# Arduino_PRO_Portenta_H7_Carrier_Shield.net
KiCad netlist of a schematic drawn in EasyEDA
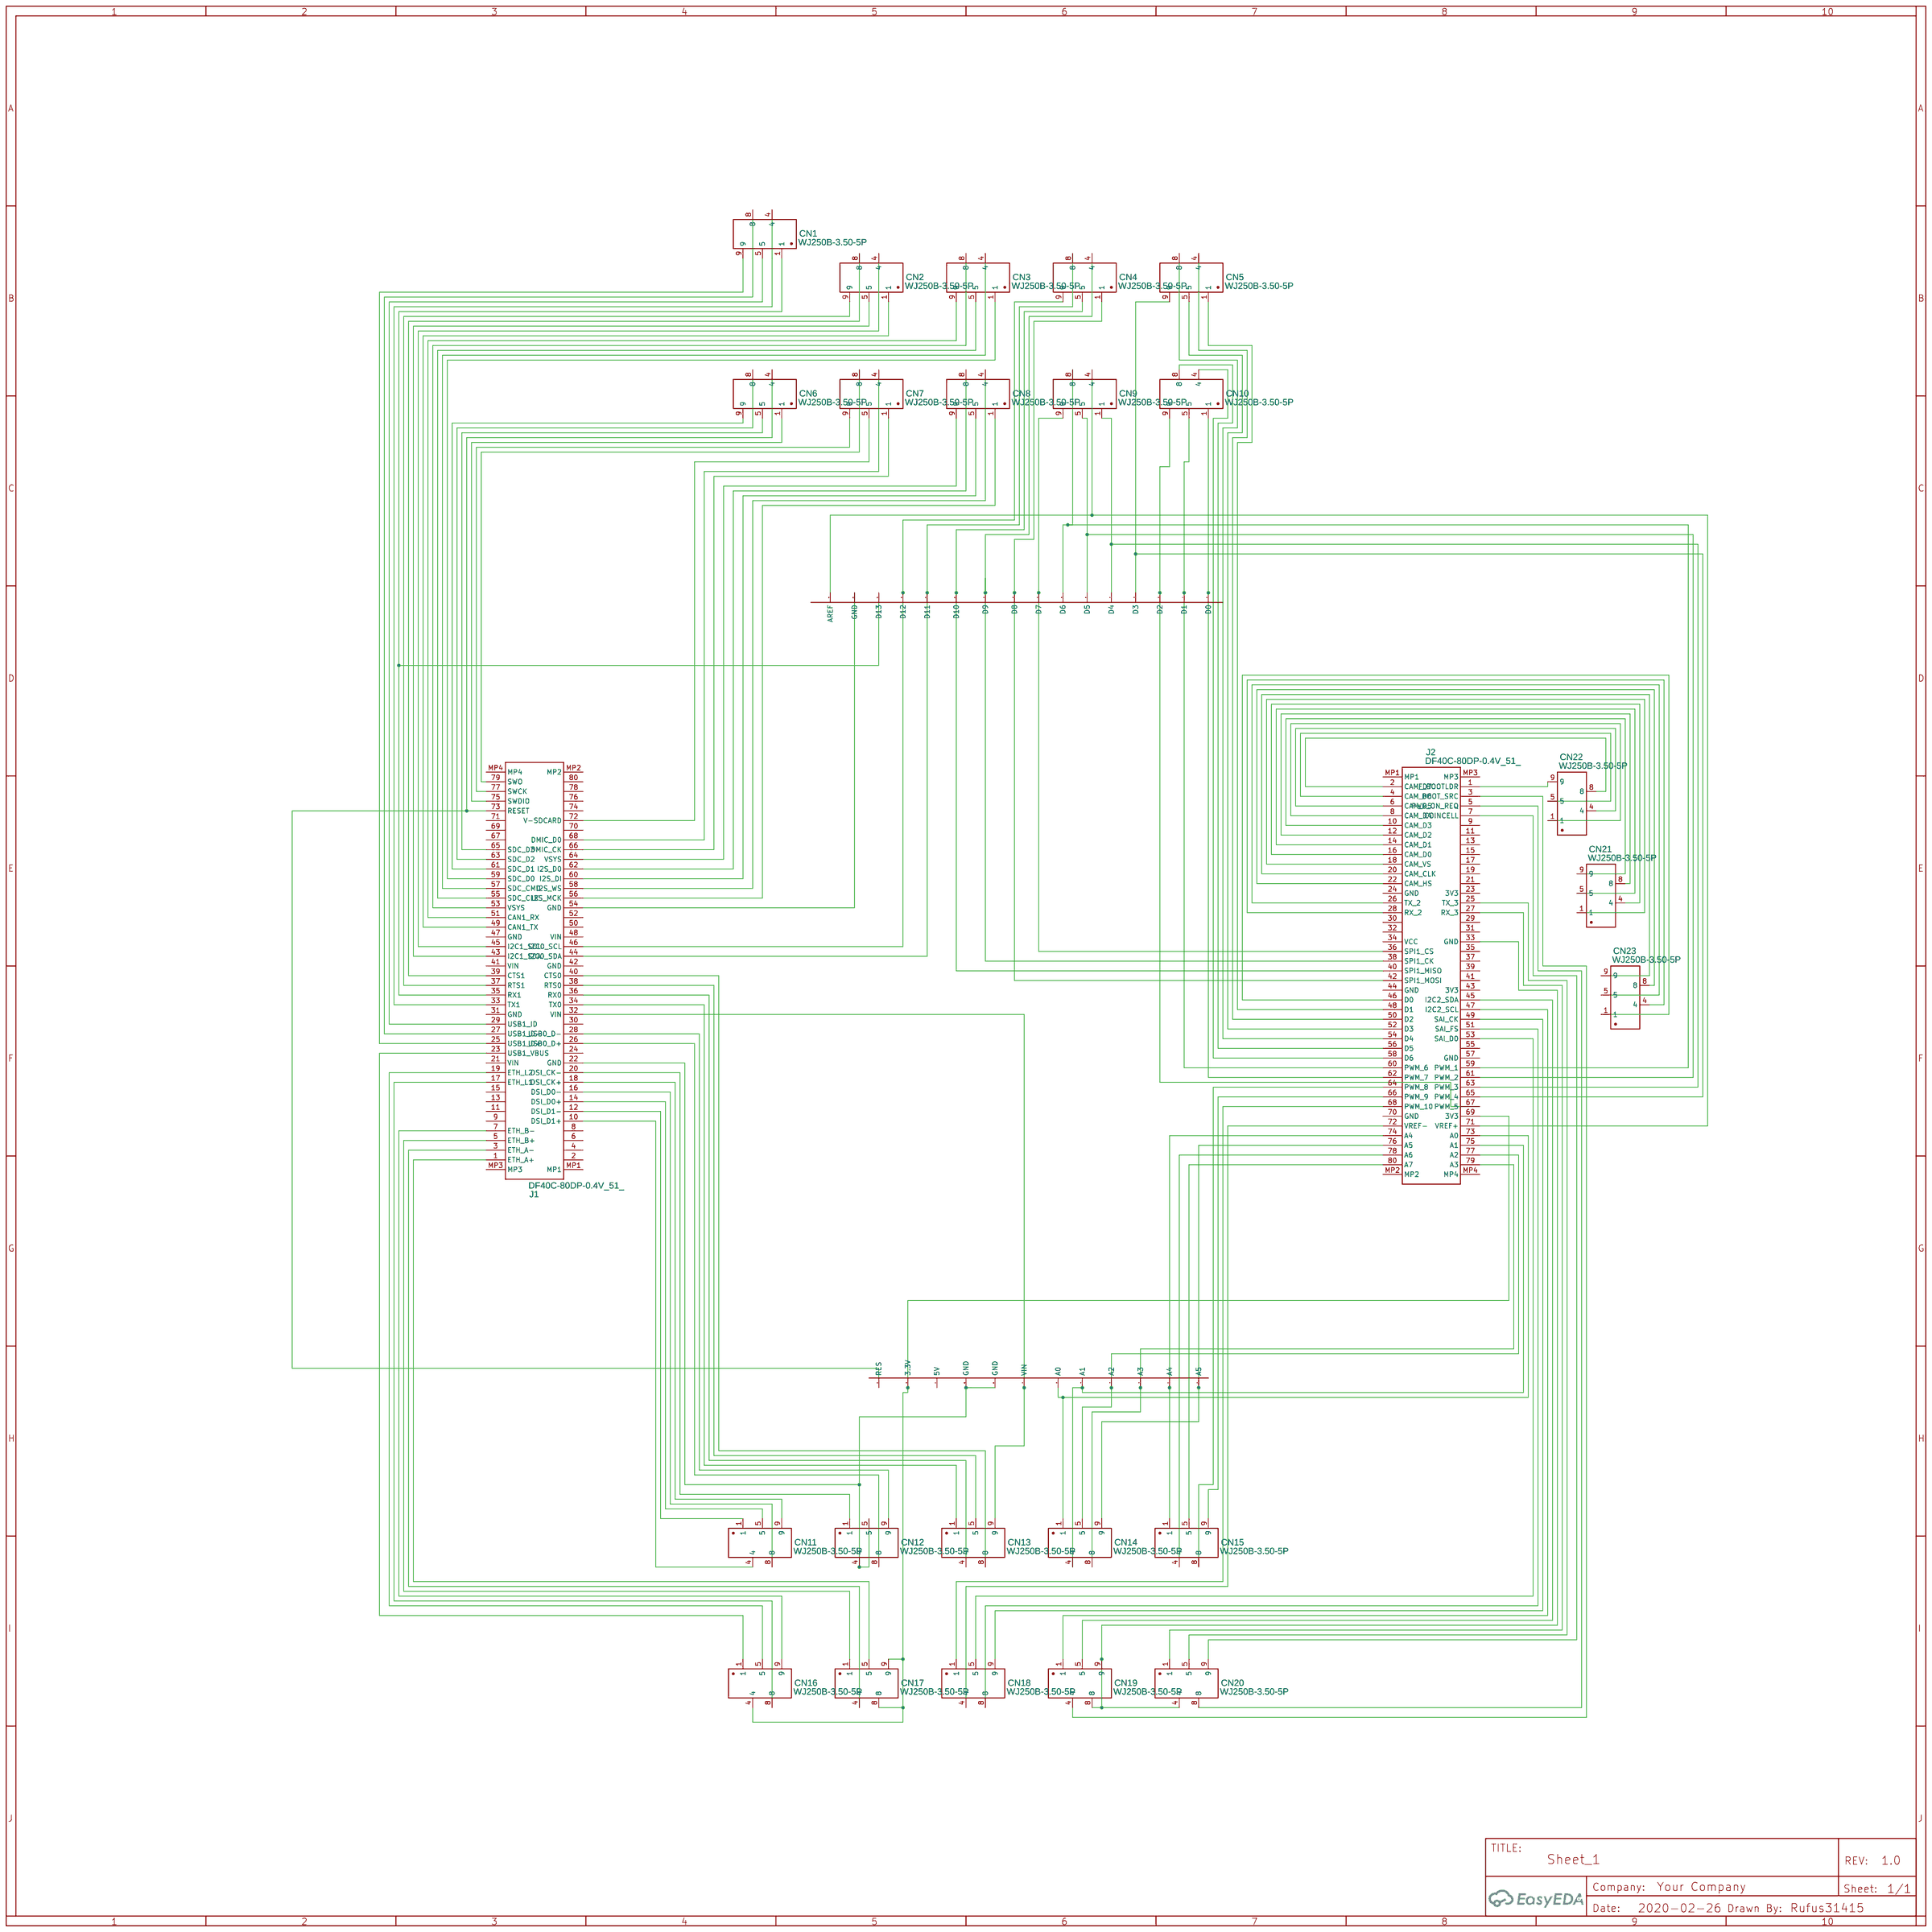
[diagram p0: schematic sheet]

(export (version "E")
  (design (tool "Eeschema 10.0.6"))
  (components
    (comp (ref "CN1")
      (value "WJ250B-3.50-5P")
      (fields (field (name "Manufacturer") "ReliaPro"))
      (libsource (lib "") (part "WJ250B-3.50-5P"))
    )
    (comp (ref "CN2")
      (value "WJ250B-3.50-5P")
      (fields (field (name "Manufacturer") "ReliaPro"))
      (libsource (lib "") (part "WJ250B-3.50-5P"))
    )
    (comp (ref "CN3")
      (value "WJ250B-3.50-5P")
      (fields (field (name "Manufacturer") "ReliaPro"))
      (libsource (lib "") (part "WJ250B-3.50-5P"))
    )
    (comp (ref "CN4")
      (value "WJ250B-3.50-5P")
      (fields (field (name "Manufacturer") "ReliaPro"))
      (libsource (lib "") (part "WJ250B-3.50-5P"))
    )
    (comp (ref "CN5")
      (value "WJ250B-3.50-5P")
      (fields (field (name "Manufacturer") "ReliaPro"))
      (libsource (lib "") (part "WJ250B-3.50-5P"))
    )
    (comp (ref "CN6")
      (value "WJ250B-3.50-5P")
      (fields (field (name "Manufacturer") "ReliaPro"))
      (libsource (lib "") (part "WJ250B-3.50-5P"))
    )
    (comp (ref "CN7")
      (value "WJ250B-3.50-5P")
      (fields (field (name "Manufacturer") "ReliaPro"))
      (libsource (lib "") (part "WJ250B-3.50-5P"))
    )
    (comp (ref "CN8")
      (value "WJ250B-3.50-5P")
      (fields (field (name "Manufacturer") "ReliaPro"))
      (libsource (lib "") (part "WJ250B-3.50-5P"))
    )
    (comp (ref "CN9")
      (value "WJ250B-3.50-5P")
      (fields (field (name "Manufacturer") "ReliaPro"))
      (libsource (lib "") (part "WJ250B-3.50-5P"))
    )
    (comp (ref "CN10")
      (value "WJ250B-3.50-5P")
      (fields (field (name "Manufacturer") "ReliaPro"))
      (libsource (lib "") (part "WJ250B-3.50-5P"))
    )
    (comp (ref "CN11")
      (value "WJ250B-3.50-5P")
      (fields (field (name "Manufacturer") "ReliaPro"))
      (libsource (lib "") (part "WJ250B-3.50-5P_1"))
    )
    (comp (ref "CN12")
      (value "WJ250B-3.50-5P")
      (fields (field (name "Manufacturer") "ReliaPro"))
      (libsource (lib "") (part "WJ250B-3.50-5P_1"))
    )
    (comp (ref "CN13")
      (value "WJ250B-3.50-5P")
      (fields (field (name "Manufacturer") "ReliaPro"))
      (libsource (lib "") (part "WJ250B-3.50-5P_1"))
    )
    (comp (ref "CN14")
      (value "WJ250B-3.50-5P")
      (fields (field (name "Manufacturer") "ReliaPro"))
      (libsource (lib "") (part "WJ250B-3.50-5P_1"))
    )
    (comp (ref "CN15")
      (value "WJ250B-3.50-5P")
      (fields (field (name "Manufacturer") "ReliaPro"))
      (libsource (lib "") (part "WJ250B-3.50-5P_1"))
    )
    (comp (ref "CN16")
      (value "WJ250B-3.50-5P")
      (fields (field (name "Manufacturer") "ReliaPro"))
      (libsource (lib "") (part "WJ250B-3.50-5P_1"))
    )
    (comp (ref "CN17")
      (value "WJ250B-3.50-5P")
      (fields (field (name "Manufacturer") "ReliaPro"))
      (libsource (lib "") (part "WJ250B-3.50-5P_1"))
    )
    (comp (ref "CN18")
      (value "WJ250B-3.50-5P")
      (fields (field (name "Manufacturer") "ReliaPro"))
      (libsource (lib "") (part "WJ250B-3.50-5P_1"))
    )
    (comp (ref "CN19")
      (value "WJ250B-3.50-5P")
      (fields (field (name "Manufacturer") "ReliaPro"))
      (libsource (lib "") (part "WJ250B-3.50-5P_1"))
    )
    (comp (ref "CN20")
      (value "WJ250B-3.50-5P")
      (fields (field (name "Manufacturer") "ReliaPro"))
      (libsource (lib "") (part "WJ250B-3.50-5P_1"))
    )
    (comp (ref "CN21")
      (value "WJ250B-3.50-5P")
      (fields (field (name "Manufacturer") "ReliaPro"))
      (libsource (lib "") (part "WJ250B-3.50-5P_2"))
    )
    (comp (ref "CN22")
      (value "WJ250B-3.50-5P")
      (fields (field (name "Manufacturer") "ReliaPro"))
      (libsource (lib "") (part "WJ250B-3.50-5P_2"))
    )
    (comp (ref "CN23")
      (value "WJ250B-3.50-5P")
      (fields (field (name "Manufacturer") "ReliaPro"))
      (libsource (lib "") (part "WJ250B-3.50-5P_2"))
    )
    (comp (ref "J1") (value "DF40C-80DP-0.4V_51_") (libsource (lib "") (part "DF40C-80DP-0.4V_51__1")))
    (comp (ref "J2") (value "DF40C-80DP-0.4V_51_") (libsource (lib "") (part "DF40C-80DP-0.4V_51_")))
    (comp (ref "U1")
      (value "ARDUINO_SHIELDNO_SILK BIG")
      (libsource (lib "") (part "ARDUINO_SHIELDNO_SILK BIG"))
    )
  )
  (nets
    (net (code "1") (name "Net-(CN3-Pad8)") (class "Default")
      (node (ref "CN3") (pin "8") (pinfunction "8_8") (pintype "unspecified"))
      (node (ref "J1") (pin "53") (pinfunction "VSYS_53") (pintype "bidirectional"))
    )
    (net (code "2") (name "Net-(CN8-Pad9)") (class "Default")
      (node (ref "CN8") (pin "9") (pinfunction "9_9") (pintype "unspecified"))
      (node (ref "J1") (pin "64") (pinfunction "VSYS_64") (pintype "bidirectional"))
    )
    (net (code "3") (name "Net-(CN12-Pad4)") (class "Default")
      (node (ref "CN12") (pin "4") (pinfunction "4_4") (pintype "unspecified"))
      (node (ref "CN12") (pin "5") (pinfunction "5_5") (pintype "unspecified"))
      (node (ref "J1") (pin "22") (pinfunction "GND_22") (pintype "bidirectional"))
      (node (ref "U1") (pin "GND@0") (pinfunction "GND_GND@0") (pintype "unspecified"))
      (node (ref "U1") (pin "GND@1") (pinfunction "GND_GND@1") (pintype "unspecified"))
    )
    (net (code "4") (name "Net-(CN13-Pad9)") (class "Default")
      (node (ref "CN13") (pin "9") (pinfunction "9_9") (pintype "unspecified"))
      (node (ref "J1") (pin "32") (pinfunction "VIN_32") (pintype "bidirectional"))
      (node (ref "U1") (pin "VIN") (pinfunction "VIN_VIN") (pintype "unspecified"))
    )
    (net (code "5") (name "Net-(CN16-Pad4)") (class "Default")
      (node (ref "CN16") (pin "4") (pinfunction "4_4") (pintype "unspecified"))
      (node (ref "CN17") (pin "8") (pinfunction "8_8") (pintype "unspecified"))
      (node (ref "CN17") (pin "9") (pinfunction "9_9") (pintype "unspecified"))
      (node (ref "J2") (pin "69") (pinfunction "3V3_69") (pintype "bidirectional"))
      (node (ref "U1") (pin "3.3V") (pinfunction "3.3V_3.3V") (pintype "unspecified"))
    )
    (net (code "6") (name "Net-(CN19-Pad8)") (class "Default")
      (node (ref "CN19") (pin "8") (pinfunction "8_8") (pintype "unspecified"))
      (node (ref "CN19") (pin "9") (pinfunction "9_9") (pintype "unspecified"))
      (node (ref "CN20") (pin "4") (pinfunction "4_4") (pintype "unspecified"))
      (node (ref "J2") (pin "33") (pinfunction "GND_33") (pintype "bidirectional"))
    )
    (net (code "7") (name "Net-(J1-CAN1_RX)") (class "Default")
      (node (ref "CN3") (pin "9") (pinfunction "9_9") (pintype "unspecified"))
      (node (ref "J1") (pin "51") (pinfunction "CAN1_RX_51") (pintype "bidirectional"))
    )
    (net (code "8") (name "Net-(J1-CAN1_TX)") (class "Default")
      (node (ref "CN2") (pin "1") (pinfunction "1_1") (pintype "unspecified"))
      (node (ref "J1") (pin "49") (pinfunction "CAN1_TX_49") (pintype "bidirectional"))
    )
    (net (code "9") (name "Net-(J1-CTS0)") (class "Default")
      (node (ref "CN13") (pin "8") (pinfunction "8_8") (pintype "unspecified"))
      (node (ref "J1") (pin "40") (pinfunction "CTS0_40") (pintype "bidirectional"))
    )
    (net (code "10") (name "Net-(J1-CTS1)") (class "Default")
      (node (ref "CN2") (pin "8") (pinfunction "8_8") (pintype "unspecified"))
      (node (ref "J1") (pin "39") (pinfunction "CTS1_39") (pintype "bidirectional"))
    )
    (net (code "11") (name "Net-(J1-DMIC_CK)") (class "Default")
      (node (ref "CN7") (pin "1") (pinfunction "1_1") (pintype "unspecified"))
      (node (ref "J1") (pin "66") (pinfunction "DMIC_CK_66") (pintype "bidirectional"))
    )
    (net (code "12") (name "Net-(J1-DMIC_D0)") (class "Default")
      (node (ref "CN7") (pin "4") (pinfunction "4_4") (pintype "unspecified"))
      (node (ref "J1") (pin "68") (pinfunction "DMIC_D0_68") (pintype "bidirectional"))
    )
    (net (code "13") (name "Net-(J1-DSI_CK+)") (class "Default")
      (node (ref "CN11") (pin "9") (pinfunction "9_9") (pintype "unspecified"))
      (node (ref "J1") (pin "18") (pinfunction "DSI_CK+_18") (pintype "bidirectional"))
    )
    (net (code "14") (name "Net-(J1-DSI_CK-)") (class "Default")
      (node (ref "CN12") (pin "1") (pinfunction "1_1") (pintype "unspecified"))
      (node (ref "J1") (pin "20") (pinfunction "DSI_CK-_20") (pintype "bidirectional"))
    )
    (net (code "15") (name "Net-(J1-DSI_D0+)") (class "Default")
      (node (ref "CN11") (pin "5") (pinfunction "5_5") (pintype "unspecified"))
      (node (ref "J1") (pin "14") (pinfunction "DSI_D0+_14") (pintype "bidirectional"))
    )
    (net (code "16") (name "Net-(J1-DSI_D0-)") (class "Default")
      (node (ref "CN11") (pin "8") (pinfunction "8_8") (pintype "unspecified"))
      (node (ref "J1") (pin "16") (pinfunction "DSI_D0-_16") (pintype "bidirectional"))
    )
    (net (code "17") (name "Net-(J1-DSI_D1+)") (class "Default")
      (node (ref "CN11") (pin "4") (pinfunction "4_4") (pintype "unspecified"))
      (node (ref "J1") (pin "10") (pinfunction "DSI_D1+_10") (pintype "bidirectional"))
    )
    (net (code "18") (name "Net-(J1-DSI_D1-)") (class "Default")
      (node (ref "CN11") (pin "1") (pinfunction "1_1") (pintype "unspecified"))
      (node (ref "J1") (pin "12") (pinfunction "DSI_D1-_12") (pintype "bidirectional"))
    )
    (net (code "19") (name "Net-(J1-ETH_A+)") (class "Default")
      (node (ref "CN17") (pin "5") (pinfunction "5_5") (pintype "unspecified"))
      (node (ref "J1") (pin "1") (pinfunction "ETH_A+_1") (pintype "bidirectional"))
    )
    (net (code "20") (name "Net-(J1-ETH_A-)") (class "Default")
      (node (ref "CN17") (pin "4") (pinfunction "4_4") (pintype "unspecified"))
      (node (ref "J1") (pin "3") (pinfunction "ETH_A-_3") (pintype "bidirectional"))
    )
    (net (code "21") (name "Net-(J1-ETH_B+)") (class "Default")
      (node (ref "CN17") (pin "1") (pinfunction "1_1") (pintype "unspecified"))
      (node (ref "J1") (pin "5") (pinfunction "ETH_B+_5") (pintype "bidirectional"))
    )
    (net (code "22") (name "Net-(J1-ETH_B-)") (class "Default")
      (node (ref "CN16") (pin "9") (pinfunction "9_9") (pintype "unspecified"))
      (node (ref "J1") (pin "7") (pinfunction "ETH_B-_7") (pintype "bidirectional"))
    )
    (net (code "23") (name "Net-(J1-ETH_L1)") (class "Default")
      (node (ref "CN16") (pin "8") (pinfunction "8_8") (pintype "unspecified"))
      (node (ref "J1") (pin "17") (pinfunction "ETH_L1_17") (pintype "bidirectional"))
    )
    (net (code "24") (name "Net-(J1-ETH_L2)") (class "Default")
      (node (ref "CN16") (pin "5") (pinfunction "5_5") (pintype "unspecified"))
      (node (ref "J1") (pin "19") (pinfunction "ETH_L2_19") (pintype "bidirectional"))
    )
    (net (code "25") (name "Net-(J1-GND-Pad54)") (class "Default")
      (node (ref "J1") (pin "54") (pinfunction "GND_54") (pintype "bidirectional"))
      (node (ref "U1") (pin "GND@2") (pinfunction "GND_GND@2") (pintype "unspecified"))
    )
    (net (code "26") (name "Net-(J1-I2C0_SCL)") (class "Default")
      (node (ref "CN4") (pin "9") (pinfunction "9_9") (pintype "unspecified"))
      (node (ref "J1") (pin "46") (pinfunction "I2C0_SCL_46") (pintype "bidirectional"))
      (node (ref "U1") (pin "D12") (pinfunction "D12_D12") (pintype "unspecified"))
    )
    (net (code "27") (name "Net-(J1-I2C0_SDA)") (class "Default")
      (node (ref "CN4") (pin "8") (pinfunction "8_8") (pintype "unspecified"))
      (node (ref "J1") (pin "44") (pinfunction "I2C0_SDA_44") (pintype "bidirectional"))
      (node (ref "U1") (pin "D11") (pinfunction "D11_D11") (pintype "unspecified"))
    )
    (net (code "28") (name "Net-(J1-I2C1_SCL)") (class "Default")
      (node (ref "CN2") (pin "4") (pinfunction "4_4") (pintype "unspecified"))
      (node (ref "J1") (pin "45") (pinfunction "I2C1_SCL_45") (pintype "bidirectional"))
    )
    (net (code "29") (name "Net-(J1-I2C1_SDA)") (class "Default")
      (node (ref "CN2") (pin "5") (pinfunction "5_5") (pintype "unspecified"))
      (node (ref "J1") (pin "43") (pinfunction "I2C1_SDA_43") (pintype "bidirectional"))
    )
    (net (code "30") (name "Net-(J1-I2S_D0)") (class "Default")
      (node (ref "CN8") (pin "8") (pinfunction "8_8") (pintype "unspecified"))
      (node (ref "J1") (pin "62") (pinfunction "I2S_D0_62") (pintype "bidirectional"))
    )
    (net (code "31") (name "Net-(J1-I2S_DI)") (class "Default")
      (node (ref "CN8") (pin "5") (pinfunction "5_5") (pintype "unspecified"))
      (node (ref "J1") (pin "60") (pinfunction "I2S_DI_60") (pintype "bidirectional"))
    )
    (net (code "32") (name "Net-(J1-I2S_MCK)") (class "Default")
      (node (ref "CN8") (pin "1") (pinfunction "1_1") (pintype "unspecified"))
      (node (ref "J1") (pin "56") (pinfunction "I2S_MCK_56") (pintype "bidirectional"))
    )
    (net (code "33") (name "Net-(J1-I2S_WS)") (class "Default")
      (node (ref "CN8") (pin "4") (pinfunction "4_4") (pintype "unspecified"))
      (node (ref "J1") (pin "58") (pinfunction "I2S_WS_58") (pintype "bidirectional"))
    )
    (net (code "34") (name "Net-(J1-RESET)") (class "Default")
      (node (ref "CN6") (pin "4") (pinfunction "4_4") (pintype "unspecified"))
      (node (ref "J1") (pin "73") (pinfunction "RESET_73") (pintype "bidirectional"))
      (node (ref "U1") (pin "RES") (pinfunction "RES_RES") (pintype "unspecified"))
    )
    (net (code "35") (name "Net-(J1-RTS0)") (class "Default")
      (node (ref "CN13") (pin "5") (pinfunction "5_5") (pintype "unspecified"))
      (node (ref "J1") (pin "38") (pinfunction "RTS0_38") (pintype "bidirectional"))
    )
    (net (code "36") (name "Net-(J1-RTS1)") (class "Default")
      (node (ref "CN2") (pin "9") (pinfunction "9_9") (pintype "unspecified"))
      (node (ref "J1") (pin "37") (pinfunction "RTS1_37") (pintype "bidirectional"))
    )
    (net (code "37") (name "Net-(J1-RX0)") (class "Default")
      (node (ref "CN13") (pin "4") (pinfunction "4_4") (pintype "unspecified"))
      (node (ref "J1") (pin "36") (pinfunction "RX0_36") (pintype "bidirectional"))
    )
    (net (code "38") (name "Net-(J1-RX1)") (class "Default")
      (node (ref "CN1") (pin "1") (pinfunction "1_1") (pintype "unspecified"))
      (node (ref "J1") (pin "35") (pinfunction "RX1_35") (pintype "bidirectional"))
      (node (ref "U1") (pin "D13") (pinfunction "D13_D13") (pintype "unspecified"))
    )
    (net (code "39") (name "Net-(J1-SDC_CLK)") (class "Default")
      (node (ref "CN3") (pin "5") (pinfunction "5_5") (pintype "unspecified"))
      (node (ref "J1") (pin "55") (pinfunction "SDC_CLK_55") (pintype "bidirectional"))
    )
    (net (code "40") (name "Net-(J1-SDC_CMD)") (class "Default")
      (node (ref "CN3") (pin "4") (pinfunction "4_4") (pintype "unspecified"))
      (node (ref "J1") (pin "57") (pinfunction "SDC_CMD_57") (pintype "bidirectional"))
    )
    (net (code "41") (name "Net-(J1-SDC_D0)") (class "Default")
      (node (ref "CN3") (pin "1") (pinfunction "1_1") (pintype "unspecified"))
      (node (ref "J1") (pin "59") (pinfunction "SDC_D0_59") (pintype "bidirectional"))
    )
    (net (code "42") (name "Net-(J1-SDC_D1)") (class "Default")
      (node (ref "CN6") (pin "9") (pinfunction "9_9") (pintype "unspecified"))
      (node (ref "J1") (pin "61") (pinfunction "SDC_D1_61") (pintype "bidirectional"))
    )
    (net (code "43") (name "Net-(J1-SDC_D2)") (class "Default")
      (node (ref "CN6") (pin "8") (pinfunction "8_8") (pintype "unspecified"))
      (node (ref "J1") (pin "63") (pinfunction "SDC_D2_63") (pintype "bidirectional"))
    )
    (net (code "44") (name "Net-(J1-SDC_D3)") (class "Default")
      (node (ref "CN6") (pin "5") (pinfunction "5_5") (pintype "unspecified"))
      (node (ref "J1") (pin "65") (pinfunction "SDC_D3_65") (pintype "bidirectional"))
    )
    (net (code "45") (name "Net-(J1-SWCK)") (class "Default")
      (node (ref "CN7") (pin "9") (pinfunction "9_9") (pintype "unspecified"))
      (node (ref "J1") (pin "77") (pinfunction "SWCK_77") (pintype "bidirectional"))
    )
    (net (code "46") (name "Net-(J1-SWDIO)") (class "Default")
      (node (ref "CN6") (pin "1") (pinfunction "1_1") (pintype "unspecified"))
      (node (ref "J1") (pin "75") (pinfunction "SWDIO_75") (pintype "bidirectional"))
    )
    (net (code "47") (name "Net-(J1-SWO)") (class "Default")
      (node (ref "CN7") (pin "8") (pinfunction "8_8") (pintype "unspecified"))
      (node (ref "J1") (pin "79") (pinfunction "SWO_79") (pintype "bidirectional"))
    )
    (net (code "48") (name "Net-(J1-TX0)") (class "Default")
      (node (ref "CN13") (pin "1") (pinfunction "1_1") (pintype "unspecified"))
      (node (ref "J1") (pin "34") (pinfunction "TX0_34") (pintype "bidirectional"))
    )
    (net (code "49") (name "Net-(J1-TX1)") (class "Default")
      (node (ref "CN1") (pin "4") (pinfunction "4_4") (pintype "unspecified"))
      (node (ref "J1") (pin "33") (pinfunction "TX1_33") (pintype "bidirectional"))
    )
    (net (code "50") (name "Net-(J1-USB0_D+)") (class "Default")
      (node (ref "CN12") (pin "8") (pinfunction "8_8") (pintype "unspecified"))
      (node (ref "J1") (pin "26") (pinfunction "USB0_D+_26") (pintype "bidirectional"))
    )
    (net (code "51") (name "Net-(J1-USB0_D-)") (class "Default")
      (node (ref "CN12") (pin "9") (pinfunction "9_9") (pintype "unspecified"))
      (node (ref "J1") (pin "28") (pinfunction "USB0_D-_28") (pintype "bidirectional"))
    )
    (net (code "52") (name "Net-(J1-USB1_D+)") (class "Default")
      (node (ref "CN1") (pin "9") (pinfunction "9_9") (pintype "unspecified"))
      (node (ref "J1") (pin "25") (pinfunction "USB1_D+_25") (pintype "bidirectional"))
    )
    (net (code "53") (name "Net-(J1-USB1_D-)") (class "Default")
      (node (ref "CN1") (pin "8") (pinfunction "8_8") (pintype "unspecified"))
      (node (ref "J1") (pin "27") (pinfunction "USB1_D-_27") (pintype "bidirectional"))
    )
    (net (code "54") (name "Net-(J1-USB1_ID)") (class "Default")
      (node (ref "CN1") (pin "5") (pinfunction "5_5") (pintype "unspecified"))
      (node (ref "J1") (pin "29") (pinfunction "USB1_ID_29") (pintype "bidirectional"))
    )
    (net (code "55") (name "Net-(J1-USB1_VBUS)") (class "Default")
      (node (ref "CN16") (pin "1") (pinfunction "1_1") (pintype "unspecified"))
      (node (ref "J1") (pin "23") (pinfunction "USB1_VBUS_23") (pintype "bidirectional"))
    )
    (net (code "56") (name "Net-(J1-V-SDCARD)") (class "Default")
      (node (ref "CN7") (pin "5") (pinfunction "5_5") (pintype "unspecified"))
      (node (ref "J1") (pin "72") (pinfunction "V-SDCARD_72") (pintype "bidirectional"))
    )
    (net (code "57") (name "Net-(J2-A0)") (class "Default")
      (node (ref "CN14") (pin "1") (pinfunction "1_1") (pintype "unspecified"))
      (node (ref "J2") (pin "73") (pinfunction "A0_73") (pintype "bidirectional"))
      (node (ref "U1") (pin "A0") (pinfunction "A0_A0") (pintype "unspecified"))
    )
    (net (code "58") (name "Net-(J2-A1)") (class "Default")
      (node (ref "CN14") (pin "4") (pinfunction "4_4") (pintype "unspecified"))
      (node (ref "J2") (pin "75") (pinfunction "A1_75") (pintype "bidirectional"))
      (node (ref "U1") (pin "A1") (pinfunction "A1_A1") (pintype "unspecified"))
    )
    (net (code "59") (name "Net-(J2-A2)") (class "Default")
      (node (ref "CN14") (pin "5") (pinfunction "5_5") (pintype "unspecified"))
      (node (ref "J2") (pin "77") (pinfunction "A2_77") (pintype "bidirectional"))
      (node (ref "U1") (pin "A2") (pinfunction "A2_A2") (pintype "unspecified"))
    )
    (net (code "60") (name "Net-(J2-A3)") (class "Default")
      (node (ref "CN14") (pin "8") (pinfunction "8_8") (pintype "unspecified"))
      (node (ref "J2") (pin "79") (pinfunction "A3_79") (pintype "bidirectional"))
      (node (ref "U1") (pin "A3") (pinfunction "A3_A3") (pintype "unspecified"))
    )
    (net (code "61") (name "Net-(J2-A4)") (class "Default")
      (node (ref "CN14") (pin "9") (pinfunction "9_9") (pintype "unspecified"))
      (node (ref "CN15") (pin "1") (pinfunction "1_1") (pintype "unspecified"))
      (node (ref "J2") (pin "74") (pinfunction "A4_74") (pintype "bidirectional"))
      (node (ref "J2") (pin "76") (pinfunction "A5_76") (pintype "bidirectional"))
      (node (ref "U1") (pin "A4") (pinfunction "A4_A4") (pintype "unspecified"))
      (node (ref "U1") (pin "A5") (pinfunction "A5_A5") (pintype "unspecified"))
    )
    (net (code "62") (name "Net-(J2-A6)") (class "Default")
      (node (ref "CN15") (pin "4") (pinfunction "4_4") (pintype "unspecified"))
      (node (ref "J2") (pin "78") (pinfunction "A6_78") (pintype "bidirectional"))
    )
    (net (code "63") (name "Net-(J2-A7)") (class "Default")
      (node (ref "CN15") (pin "5") (pinfunction "5_5") (pintype "unspecified"))
      (node (ref "J2") (pin "80") (pinfunction "A7_80") (pintype "bidirectional"))
    )
    (net (code "64") (name "Net-(J2-BOOT_SRC)") (class "Default")
      (node (ref "CN19") (pin "4") (pinfunction "4_4") (pintype "unspecified"))
      (node (ref "J2") (pin "3") (pinfunction "BOOT_SRC_3") (pintype "bidirectional"))
    )
    (net (code "65") (name "Net-(J2-CAM_CLK)") (class "Default")
      (node (ref "CN23") (pin "9") (pinfunction "9_9") (pintype "unspecified"))
      (node (ref "J2") (pin "20") (pinfunction "CAM_CLK_20") (pintype "bidirectional"))
    )
    (net (code "66") (name "Net-(J2-CAM_D0)") (class "Default")
      (node (ref "CN21") (pin "4") (pinfunction "4_4") (pintype "unspecified"))
      (node (ref "J2") (pin "16") (pinfunction "CAM_D0_16") (pintype "bidirectional"))
    )
    (net (code "67") (name "Net-(J2-CAM_D1)") (class "Default")
      (node (ref "CN21") (pin "5") (pinfunction "5_5") (pintype "unspecified"))
      (node (ref "J2") (pin "14") (pinfunction "CAM_D1_14") (pintype "bidirectional"))
    )
    (net (code "68") (name "Net-(J2-CAM_D2)") (class "Default")
      (node (ref "CN21") (pin "8") (pinfunction "8_8") (pintype "unspecified"))
      (node (ref "J2") (pin "12") (pinfunction "CAM_D2_12") (pintype "bidirectional"))
    )
    (net (code "69") (name "Net-(J2-CAM_D3)") (class "Default")
      (node (ref "CN21") (pin "9") (pinfunction "9_9") (pintype "unspecified"))
      (node (ref "J2") (pin "10") (pinfunction "CAM_D3_10") (pintype "bidirectional"))
    )
    (net (code "70") (name "Net-(J2-CAM_D4)") (class "Default")
      (node (ref "CN22") (pin "1") (pinfunction "1_1") (pintype "unspecified"))
      (node (ref "J2") (pin "8") (pinfunction "CAM_D4_8") (pintype "bidirectional"))
    )
    (net (code "71") (name "Net-(J2-CAM_D5)") (class "Default")
      (node (ref "CN22") (pin "4") (pinfunction "4_4") (pintype "unspecified"))
      (node (ref "J2") (pin "6") (pinfunction "CAM_D5_6") (pintype "bidirectional"))
    )
    (net (code "72") (name "Net-(J2-CAM_D6)") (class "Default")
      (node (ref "CN22") (pin "5") (pinfunction "5_5") (pintype "unspecified"))
      (node (ref "J2") (pin "4") (pinfunction "CAM_D6_4") (pintype "bidirectional"))
    )
    (net (code "73") (name "Net-(J2-CAM_D7)") (class "Default")
      (node (ref "CN22") (pin "8") (pinfunction "8_8") (pintype "unspecified"))
      (node (ref "J2") (pin "2") (pinfunction "CAM_D7_2") (pintype "bidirectional"))
    )
    (net (code "74") (name "Net-(J2-CAM_HS)") (class "Default")
      (node (ref "CN23") (pin "8") (pinfunction "8_8") (pintype "unspecified"))
      (node (ref "J2") (pin "22") (pinfunction "CAM_HS_22") (pintype "bidirectional"))
    )
    (net (code "75") (name "Net-(J2-CAM_VS)") (class "Default")
      (node (ref "CN21") (pin "1") (pinfunction "1_1") (pintype "unspecified"))
      (node (ref "J2") (pin "18") (pinfunction "CAM_VS_18") (pintype "bidirectional"))
    )
    (net (code "76") (name "Net-(J2-COINCELL)") (class "Default")
      (node (ref "CN20") (pin "9") (pinfunction "9_9") (pintype "unspecified"))
      (node (ref "J2") (pin "7") (pinfunction "COINCELL_7") (pintype "bidirectional"))
    )
    (net (code "77") (name "Net-(J2-D0)") (class "Default")
      (node (ref "CN23") (pin "1") (pinfunction "1_1") (pintype "unspecified"))
      (node (ref "J2") (pin "46") (pinfunction "D0_46") (pintype "bidirectional"))
    )
    (net (code "78") (name "Net-(J2-D1)") (class "Default")
      (node (ref "CN5") (pin "1") (pinfunction "1_1") (pintype "unspecified"))
      (node (ref "J2") (pin "48") (pinfunction "D1_48") (pintype "bidirectional"))
    )
    (net (code "79") (name "Net-(J2-D2)") (class "Default")
      (node (ref "CN5") (pin "4") (pinfunction "4_4") (pintype "unspecified"))
      (node (ref "J2") (pin "50") (pinfunction "D2_50") (pintype "bidirectional"))
    )
    (net (code "80") (name "Net-(J2-D3)") (class "Default")
      (node (ref "CN5") (pin "5") (pinfunction "5_5") (pintype "unspecified"))
      (node (ref "J2") (pin "52") (pinfunction "D3_52") (pintype "bidirectional"))
    )
    (net (code "81") (name "Net-(J2-D4)") (class "Default")
      (node (ref "CN5") (pin "8") (pinfunction "8_8") (pintype "unspecified"))
      (node (ref "J2") (pin "54") (pinfunction "D4_54") (pintype "bidirectional"))
    )
    (net (code "82") (name "Net-(J2-D5)") (class "Default")
      (node (ref "CN10") (pin "8") (pinfunction "8_8") (pintype "unspecified"))
      (node (ref "J2") (pin "56") (pinfunction "D5_56") (pintype "bidirectional"))
    )
    (net (code "83") (name "Net-(J2-D6)") (class "Default")
      (node (ref "CN10") (pin "4") (pinfunction "4_4") (pintype "unspecified"))
      (node (ref "J2") (pin "58") (pinfunction "D6_58") (pintype "bidirectional"))
    )
    (net (code "84") (name "Net-(J2-F_BOOTLDR)") (class "Default")
      (node (ref "CN22") (pin "9") (pinfunction "9_9") (pintype "unspecified"))
      (node (ref "J2") (pin "1") (pinfunction "F_BOOTLDR_1") (pintype "bidirectional"))
    )
    (net (code "85") (name "Net-(J2-I2C2_SCL)") (class "Default")
      (node (ref "CN19") (pin "1") (pinfunction "1_1") (pintype "unspecified"))
      (node (ref "J2") (pin "47") (pinfunction "I2C2_SCL_47") (pintype "bidirectional"))
    )
    (net (code "86") (name "Net-(J2-I2C2_SDA)") (class "Default")
      (node (ref "CN19") (pin "5") (pinfunction "5_5") (pintype "unspecified"))
      (node (ref "J2") (pin "45") (pinfunction "I2C2_SDA_45") (pintype "bidirectional"))
    )
    (net (code "87") (name "Net-(J2-PWM_1)") (class "Default")
      (node (ref "CN9") (pin "8") (pinfunction "8_8") (pintype "unspecified"))
      (node (ref "J2") (pin "59") (pinfunction "PWM_1_59") (pintype "bidirectional"))
      (node (ref "U1") (pin "D6") (pinfunction "D6_D6") (pintype "unspecified"))
    )
    (net (code "88") (name "Net-(J2-PWM_2)") (class "Default")
      (node (ref "CN9") (pin "5") (pinfunction "5_5") (pintype "unspecified"))
      (node (ref "J2") (pin "61") (pinfunction "PWM_2_61") (pintype "bidirectional"))
      (node (ref "U1") (pin "D5") (pinfunction "D5_D5") (pintype "unspecified"))
    )
    (net (code "89") (name "Net-(J2-PWM_3)") (class "Default")
      (node (ref "CN9") (pin "1") (pinfunction "1_1") (pintype "unspecified"))
      (node (ref "J2") (pin "63") (pinfunction "PWM_3_63") (pintype "bidirectional"))
      (node (ref "U1") (pin "D4") (pinfunction "D4_D4") (pintype "unspecified"))
    )
    (net (code "90") (name "Net-(J2-PWM_4)") (class "Default")
      (node (ref "CN5") (pin "9") (pinfunction "9_9") (pintype "unspecified"))
      (node (ref "J2") (pin "65") (pinfunction "PWM_4_65") (pintype "bidirectional"))
      (node (ref "U1") (pin "D3") (pinfunction "D3_D3") (pintype "unspecified"))
    )
    (net (code "91") (name "Net-(J2-PWM_5)") (class "Default")
      (node (ref "CN10") (pin "9") (pinfunction "9_9") (pintype "unspecified"))
      (node (ref "J2") (pin "67") (pinfunction "PWM_5_67") (pintype "bidirectional"))
      (node (ref "U1") (pin "D2") (pinfunction "D2_D2") (pintype "unspecified"))
    )
    (net (code "92") (name "Net-(J2-PWM_6)") (class "Default")
      (node (ref "CN10") (pin "5") (pinfunction "5_5") (pintype "unspecified"))
      (node (ref "J2") (pin "60") (pinfunction "PWM_6_60") (pintype "bidirectional"))
      (node (ref "U1") (pin "TX") (pinfunction "D1_TX") (pintype "unspecified"))
    )
    (net (code "93") (name "Net-(J2-PWM_7)") (class "Default")
      (node (ref "CN10") (pin "1") (pinfunction "1_1") (pintype "unspecified"))
      (node (ref "J2") (pin "62") (pinfunction "PWM_7_62") (pintype "bidirectional"))
      (node (ref "U1") (pin "RX") (pinfunction "D0_RX") (pintype "unspecified"))
    )
    (net (code "94") (name "Net-(J2-PWM_8)") (class "Default")
      (node (ref "CN15") (pin "8") (pinfunction "8_8") (pintype "unspecified"))
      (node (ref "J2") (pin "64") (pinfunction "PWM_8_64") (pintype "bidirectional"))
    )
    (net (code "95") (name "Net-(J2-PWM_9)") (class "Default")
      (node (ref "CN15") (pin "9") (pinfunction "9_9") (pintype "unspecified"))
      (node (ref "J2") (pin "66") (pinfunction "PWM_9_66") (pintype "bidirectional"))
    )
    (net (code "96") (name "Net-(J2-PWM_10)") (class "Default")
      (node (ref "CN18") (pin "1") (pinfunction "1_1") (pintype "unspecified"))
      (node (ref "J2") (pin "68") (pinfunction "PWM_10_68") (pintype "bidirectional"))
    )
    (net (code "97") (name "Net-(J2-PWR_ON_REQ)") (class "Default")
      (node (ref "CN20") (pin "8") (pinfunction "8_8") (pintype "unspecified"))
      (node (ref "J2") (pin "5") (pinfunction "PWR_ON_REQ_5") (pintype "bidirectional"))
    )
    (net (code "98") (name "Net-(J2-RX_2)") (class "Default")
      (node (ref "CN23") (pin "4") (pinfunction "4_4") (pintype "unspecified"))
      (node (ref "J2") (pin "28") (pinfunction "RX_2_28") (pintype "bidirectional"))
    )
    (net (code "99") (name "Net-(J2-RX_3)") (class "Default")
      (node (ref "CN20") (pin "1") (pinfunction "1_1") (pintype "unspecified"))
      (node (ref "J2") (pin "27") (pinfunction "RX_3_27") (pintype "bidirectional"))
    )
    (net (code "100") (name "Net-(J2-SAI_CK)") (class "Default")
      (node (ref "CN18") (pin "9") (pinfunction "9_9") (pintype "unspecified"))
      (node (ref "J2") (pin "49") (pinfunction "SAI_CK_49") (pintype "bidirectional"))
    )
    (net (code "101") (name "Net-(J2-SAI_D0)") (class "Default")
      (node (ref "CN18") (pin "5") (pinfunction "5_5") (pintype "unspecified"))
      (node (ref "J2") (pin "53") (pinfunction "SAI_D0_53") (pintype "bidirectional"))
    )
    (net (code "102") (name "Net-(J2-SAI_FS)") (class "Default")
      (node (ref "CN18") (pin "8") (pinfunction "8_8") (pintype "unspecified"))
      (node (ref "J2") (pin "51") (pinfunction "SAI_FS_51") (pintype "bidirectional"))
    )
    (net (code "103") (name "Net-(J2-SPI1_CK)") (class "Default")
      (node (ref "CN4") (pin "4") (pinfunction "4_4") (pintype "unspecified"))
      (node (ref "J2") (pin "38") (pinfunction "SPI1_CK_38") (pintype "bidirectional"))
      (node (ref "U1") (pin "D9") (pinfunction "D9_D9") (pintype "unspecified"))
    )
    (net (code "104") (name "Net-(J2-SPI1_CS)") (class "Default")
      (node (ref "CN9") (pin "9") (pinfunction "9_9") (pintype "unspecified"))
      (node (ref "J2") (pin "36") (pinfunction "SPI1_CS_36") (pintype "bidirectional"))
      (node (ref "U1") (pin "D7") (pinfunction "D7_D7") (pintype "unspecified"))
    )
    (net (code "105") (name "Net-(J2-SPI1_MISO)") (class "Default")
      (node (ref "CN4") (pin "5") (pinfunction "5_5") (pintype "unspecified"))
      (node (ref "J2") (pin "40") (pinfunction "SPI1_MISO_40") (pintype "bidirectional"))
      (node (ref "U1") (pin "D10") (pinfunction "D10_D10") (pintype "unspecified"))
    )
    (net (code "106") (name "Net-(J2-SPI1_MOSI)") (class "Default")
      (node (ref "CN4") (pin "1") (pinfunction "1_1") (pintype "unspecified"))
      (node (ref "J2") (pin "42") (pinfunction "SPI1_MOSI_42") (pintype "bidirectional"))
      (node (ref "U1") (pin "D8") (pinfunction "D8_D8") (pintype "unspecified"))
    )
    (net (code "107") (name "Net-(J2-TX_2)") (class "Default")
      (node (ref "CN23") (pin "5") (pinfunction "5_5") (pintype "unspecified"))
      (node (ref "J2") (pin "26") (pinfunction "TX_2_26") (pintype "bidirectional"))
    )
    (net (code "108") (name "Net-(J2-TX_3)") (class "Default")
      (node (ref "CN20") (pin "5") (pinfunction "5_5") (pintype "unspecified"))
      (node (ref "J2") (pin "25") (pinfunction "TX_3_25") (pintype "bidirectional"))
    )
    (net (code "109") (name "Net-(J2-VREF+)") (class "Default")
      (node (ref "CN9") (pin "4") (pinfunction "4_4") (pintype "unspecified"))
      (node (ref "J2") (pin "71") (pinfunction "VREF+_71") (pintype "bidirectional"))
      (node (ref "U1") (pin "AREF") (pinfunction "AREF_AREF") (pintype "unspecified"))
    )
    (net (code "110") (name "Net-(J2-VREF-)") (class "Default")
      (node (ref "CN18") (pin "4") (pinfunction "4_4") (pintype "unspecified"))
      (node (ref "J2") (pin "72") (pinfunction "VREF-_72") (pintype "bidirectional"))
    )
    (net (code "111") (name "unconnected-(J1-GND-Pad31)") (class "Default")
      (node (ref "J1") (pin "31") (pinfunction "GND_31") (pintype "bidirectional"))
    )
    (net (code "112") (name "unconnected-(J1-GND-Pad42)") (class "Default")
      (node (ref "J1") (pin "42") (pinfunction "GND_42") (pintype "bidirectional"))
    )
    (net (code "113") (name "unconnected-(J1-GND-Pad47)") (class "Default")
      (node (ref "J1") (pin "47") (pinfunction "GND_47") (pintype "bidirectional"))
    )
    (net (code "114") (name "unconnected-(J1-Pad2)") (class "Default")
      (node (ref "J1") (pin "2") (pintype "bidirectional"))
    )
    (net (code "115") (name "unconnected-(J1-Pad4)") (class "Default")
      (node (ref "J1") (pin "4") (pintype "bidirectional"))
    )
    (net (code "116") (name "unconnected-(J1-Pad6)") (class "Default")
      (node (ref "J1") (pin "6") (pintype "bidirectional"))
    )
    (net (code "117") (name "unconnected-(J1-Pad8)") (class "Default")
      (node (ref "J1") (pin "8") (pintype "bidirectional"))
    )
    (net (code "118") (name "unconnected-(J1-Pad9)") (class "Default")
      (node (ref "J1") (pin "9") (pintype "bidirectional"))
    )
    (net (code "119") (name "unconnected-(J1-Pad11)") (class "Default")
      (node (ref "J1") (pin "11") (pintype "bidirectional"))
    )
    (net (code "120") (name "unconnected-(J1-Pad13)") (class "Default")
      (node (ref "J1") (pin "13") (pintype "bidirectional"))
    )
    (net (code "121") (name "unconnected-(J1-Pad15)") (class "Default")
      (node (ref "J1") (pin "15") (pintype "bidirectional"))
    )
    (net (code "122") (name "unconnected-(J1-Pad24)") (class "Default")
      (node (ref "J1") (pin "24") (pintype "bidirectional"))
    )
    (net (code "123") (name "unconnected-(J1-Pad30)") (class "Default")
      (node (ref "J1") (pin "30") (pintype "bidirectional"))
    )
    (net (code "124") (name "unconnected-(J1-Pad50)") (class "Default")
      (node (ref "J1") (pin "50") (pintype "bidirectional"))
    )
    (net (code "125") (name "unconnected-(J1-Pad52)") (class "Default")
      (node (ref "J1") (pin "52") (pintype "bidirectional"))
    )
    (net (code "126") (name "unconnected-(J1-Pad67)") (class "Default")
      (node (ref "J1") (pin "67") (pintype "bidirectional"))
    )
    (net (code "127") (name "unconnected-(J1-Pad69)") (class "Default")
      (node (ref "J1") (pin "69") (pintype "bidirectional"))
    )
    (net (code "128") (name "unconnected-(J1-Pad70)") (class "Default")
      (node (ref "J1") (pin "70") (pintype "bidirectional"))
    )
    (net (code "129") (name "unconnected-(J1-Pad71)") (class "Default")
      (node (ref "J1") (pin "71") (pintype "bidirectional"))
    )
    (net (code "130") (name "unconnected-(J1-Pad74)") (class "Default")
      (node (ref "J1") (pin "74") (pintype "bidirectional"))
    )
    (net (code "131") (name "unconnected-(J1-Pad76)") (class "Default")
      (node (ref "J1") (pin "76") (pintype "bidirectional"))
    )
    (net (code "132") (name "unconnected-(J1-Pad78)") (class "Default")
      (node (ref "J1") (pin "78") (pintype "bidirectional"))
    )
    (net (code "133") (name "unconnected-(J1-Pad80)") (class "Default")
      (node (ref "J1") (pin "80") (pintype "bidirectional"))
    )
    (net (code "134") (name "unconnected-(J1-PadMP1)") (class "Default")
      (node (ref "J1") (pin "MP1") (pinfunction "MP1_MP1") (pintype "bidirectional"))
    )
    (net (code "135") (name "unconnected-(J1-PadMP2)") (class "Default")
      (node (ref "J1") (pin "MP2") (pinfunction "MP2_MP2") (pintype "bidirectional"))
    )
    (net (code "136") (name "unconnected-(J1-PadMP3)") (class "Default")
      (node (ref "J1") (pin "MP3") (pinfunction "MP3_MP3") (pintype "bidirectional"))
    )
    (net (code "137") (name "unconnected-(J1-PadMP4)") (class "Default")
      (node (ref "J1") (pin "MP4") (pinfunction "MP4_MP4") (pintype "bidirectional"))
    )
    (net (code "138") (name "unconnected-(J1-VIN-Pad21)") (class "Default")
      (node (ref "J1") (pin "21") (pinfunction "VIN_21") (pintype "bidirectional"))
    )
    (net (code "139") (name "unconnected-(J1-VIN-Pad41)") (class "Default")
      (node (ref "J1") (pin "41") (pinfunction "VIN_41") (pintype "bidirectional"))
    )
    (net (code "140") (name "unconnected-(J1-VIN-Pad48)") (class "Default")
      (node (ref "J1") (pin "48") (pinfunction "VIN_48") (pintype "bidirectional"))
    )
    (net (code "141") (name "unconnected-(J2-3V3-Pad23)") (class "Default")
      (node (ref "J2") (pin "23") (pinfunction "3V3_23") (pintype "bidirectional"))
    )
    (net (code "142") (name "unconnected-(J2-3V3-Pad43)") (class "Default")
      (node (ref "J2") (pin "43") (pinfunction "3V3_43") (pintype "bidirectional"))
    )
    (net (code "143") (name "unconnected-(J2-GND-Pad24)") (class "Default")
      (node (ref "J2") (pin "24") (pinfunction "GND_24") (pintype "bidirectional"))
    )
    (net (code "144") (name "unconnected-(J2-GND-Pad44)") (class "Default")
      (node (ref "J2") (pin "44") (pinfunction "GND_44") (pintype "bidirectional"))
    )
    (net (code "145") (name "unconnected-(J2-GND-Pad57)") (class "Default")
      (node (ref "J2") (pin "57") (pinfunction "GND_57") (pintype "bidirectional"))
    )
    (net (code "146") (name "unconnected-(J2-GND-Pad70)") (class "Default")
      (node (ref "J2") (pin "70") (pinfunction "GND_70") (pintype "bidirectional"))
    )
    (net (code "147") (name "unconnected-(J2-Pad9)") (class "Default")
      (node (ref "J2") (pin "9") (pintype "bidirectional"))
    )
    (net (code "148") (name "unconnected-(J2-Pad11)") (class "Default")
      (node (ref "J2") (pin "11") (pintype "bidirectional"))
    )
    (net (code "149") (name "unconnected-(J2-Pad13)") (class "Default")
      (node (ref "J2") (pin "13") (pintype "bidirectional"))
    )
    (net (code "150") (name "unconnected-(J2-Pad15)") (class "Default")
      (node (ref "J2") (pin "15") (pintype "bidirectional"))
    )
    (net (code "151") (name "unconnected-(J2-Pad17)") (class "Default")
      (node (ref "J2") (pin "17") (pintype "bidirectional"))
    )
    (net (code "152") (name "unconnected-(J2-Pad19)") (class "Default")
      (node (ref "J2") (pin "19") (pintype "bidirectional"))
    )
    (net (code "153") (name "unconnected-(J2-Pad21)") (class "Default")
      (node (ref "J2") (pin "21") (pintype "bidirectional"))
    )
    (net (code "154") (name "unconnected-(J2-Pad29)") (class "Default")
      (node (ref "J2") (pin "29") (pintype "bidirectional"))
    )
    (net (code "155") (name "unconnected-(J2-Pad30)") (class "Default")
      (node (ref "J2") (pin "30") (pintype "bidirectional"))
    )
    (net (code "156") (name "unconnected-(J2-Pad31)") (class "Default")
      (node (ref "J2") (pin "31") (pintype "bidirectional"))
    )
    (net (code "157") (name "unconnected-(J2-Pad32)") (class "Default")
      (node (ref "J2") (pin "32") (pintype "bidirectional"))
    )
    (net (code "158") (name "unconnected-(J2-Pad35)") (class "Default")
      (node (ref "J2") (pin "35") (pintype "bidirectional"))
    )
    (net (code "159") (name "unconnected-(J2-Pad37)") (class "Default")
      (node (ref "J2") (pin "37") (pintype "bidirectional"))
    )
    (net (code "160") (name "unconnected-(J2-Pad39)") (class "Default")
      (node (ref "J2") (pin "39") (pintype "bidirectional"))
    )
    (net (code "161") (name "unconnected-(J2-Pad41)") (class "Default")
      (node (ref "J2") (pin "41") (pintype "bidirectional"))
    )
    (net (code "162") (name "unconnected-(J2-Pad55)") (class "Default")
      (node (ref "J2") (pin "55") (pintype "bidirectional"))
    )
    (net (code "163") (name "unconnected-(J2-PadMP1)") (class "Default")
      (node (ref "J2") (pin "MP1") (pinfunction "MP1_MP1") (pintype "bidirectional"))
    )
    (net (code "164") (name "unconnected-(J2-PadMP2)") (class "Default")
      (node (ref "J2") (pin "MP2") (pinfunction "MP2_MP2") (pintype "bidirectional"))
    )
    (net (code "165") (name "unconnected-(J2-PadMP3)") (class "Default")
      (node (ref "J2") (pin "MP3") (pinfunction "MP3_MP3") (pintype "bidirectional"))
    )
    (net (code "166") (name "unconnected-(J2-PadMP4)") (class "Default")
      (node (ref "J2") (pin "MP4") (pinfunction "MP4_MP4") (pintype "bidirectional"))
    )
    (net (code "167") (name "unconnected-(J2-VCC-Pad34)") (class "Default")
      (node (ref "J2") (pin "34") (pinfunction "VCC_34") (pintype "bidirectional"))
    )
    (net (code "168") (name "unconnected-(U1-Pad5V)") (class "Default")
      (node (ref "U1") (pin "5V") (pinfunction "5V_5V") (pintype "unspecified"))
    )
  )
)
